# MAGI_sDIPBoard-Python.net
KiCad netlist of a schematic drawn in Altium Designer
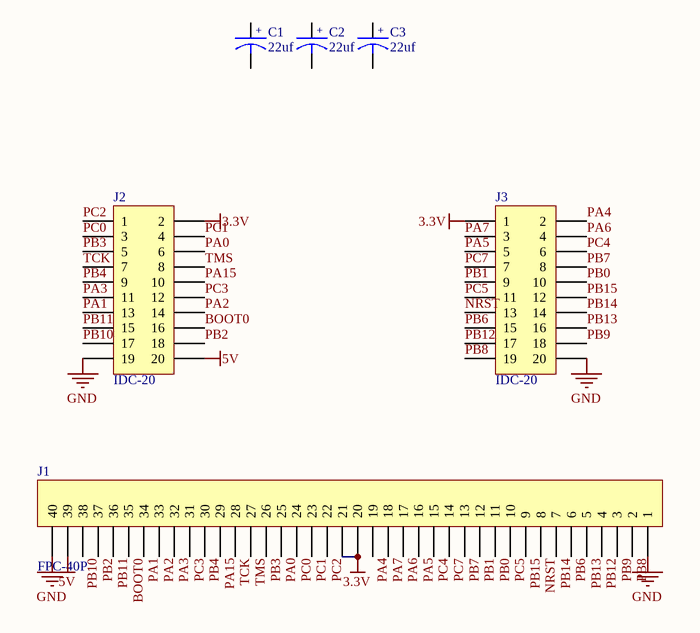
[diagram p0: MAGI'sDIPBoard-Python.SchDoc]

(export (version "E")
  (design (tool "Eeschema 10.0.6"))
  (components
    (comp (ref "C1")
      (value "22uf")
      (footprint "C1210_N")
      (description "Capacitor")
      (libsource (lib "电容器") (part "CAPACITOR POL"))
    )
    (comp (ref "C2")
      (value "22uf")
      (footprint "C1210_N")
      (description "Capacitor")
      (libsource (lib "电容器") (part "CAPACITOR POL"))
    )
    (comp (ref "C3")
      (value "22uf")
      (footprint "C1210_N")
      (description "Capacitor")
      (libsource (lib "电容器") (part "CAPACITOR POL"))
    )
    (comp (ref "J1")
      (value "FPC-40P")
      (footprint "FFC/SM0.5-2H40")
      (description "Connector")
      (libsource (lib "CON系列") (part "CON40"))
    )
    (comp (ref "J2") (value "IDC-20") (footprint "IDC-20") (libsource (lib "CON系列") (part "IDC-20")))
    (comp (ref "J3") (value "IDC-20") (footprint "IDC-20") (libsource (lib "CON系列") (part "IDC-20")))
  )
  (nets
    (net (code "1") (name "/BOOT0") (class "Default")
      (node (ref "J1") (pin "35") (pinfunction "35_35") (pintype "passive"))
      (node (ref "J2") (pin "16") (pinfunction "16_16") (pintype "passive"))
    )
    (net (code "2") (name "/NRST") (class "Default")
      (node (ref "J1") (pin "8") (pinfunction "8_8") (pintype "passive"))
      (node (ref "J3") (pin "13") (pinfunction "13_13") (pintype "passive"))
    )
    (net (code "3") (name "/PA0") (class "Default")
      (node (ref "J1") (pin "25") (pinfunction "25_25") (pintype "passive"))
      (node (ref "J2") (pin "6") (pinfunction "6_6") (pintype "passive"))
    )
    (net (code "4") (name "/PA1") (class "Default")
      (node (ref "J1") (pin "34") (pinfunction "34_34") (pintype "passive"))
      (node (ref "J2") (pin "13") (pinfunction "13_13") (pintype "passive"))
    )
    (net (code "5") (name "/PA2") (class "Default")
      (node (ref "J1") (pin "33") (pinfunction "33_33") (pintype "passive"))
      (node (ref "J2") (pin "14") (pinfunction "14_14") (pintype "passive"))
    )
    (net (code "6") (name "/PA3") (class "Default")
      (node (ref "J1") (pin "32") (pinfunction "32_32") (pintype "passive"))
      (node (ref "J2") (pin "11") (pinfunction "11_11") (pintype "passive"))
    )
    (net (code "7") (name "/PA4") (class "Default")
      (node (ref "J1") (pin "19") (pinfunction "19_19") (pintype "passive"))
      (node (ref "J3") (pin "2") (pinfunction "2_2") (pintype "passive"))
    )
    (net (code "8") (name "/PA5") (class "Default")
      (node (ref "J1") (pin "16") (pinfunction "16_16") (pintype "passive"))
      (node (ref "J3") (pin "5") (pinfunction "5_5") (pintype "passive"))
    )
    (net (code "9") (name "/PA6") (class "Default")
      (node (ref "J1") (pin "17") (pinfunction "17_17") (pintype "passive"))
      (node (ref "J3") (pin "4") (pinfunction "4_4") (pintype "passive"))
    )
    (net (code "10") (name "/PA7") (class "Default")
      (node (ref "J1") (pin "18") (pinfunction "18_18") (pintype "passive"))
      (node (ref "J3") (pin "3") (pinfunction "3_3") (pintype "passive"))
    )
    (net (code "11") (name "/PA15") (class "Default")
      (node (ref "J1") (pin "29") (pinfunction "29_29") (pintype "passive"))
      (node (ref "J2") (pin "10") (pinfunction "10_10") (pintype "passive"))
    )
    (net (code "12") (name "/PB0") (class "Default")
      (node (ref "J1") (pin "11") (pinfunction "11_11") (pintype "passive"))
      (node (ref "J3") (pin "10") (pinfunction "10_10") (pintype "passive"))
    )
    (net (code "13") (name "/PB1") (class "Default")
      (node (ref "J1") (pin "12") (pinfunction "12_12") (pintype "passive"))
      (node (ref "J3") (pin "9") (pinfunction "9_9") (pintype "passive"))
    )
    (net (code "14") (name "/PB2") (class "Default")
      (node (ref "J1") (pin "37") (pinfunction "37_37") (pintype "passive"))
      (node (ref "J2") (pin "18") (pinfunction "18_18") (pintype "passive"))
    )
    (net (code "15") (name "/PB3") (class "Default")
      (node (ref "J1") (pin "26") (pinfunction "26_26") (pintype "passive"))
      (node (ref "J2") (pin "5") (pinfunction "5_5") (pintype "passive"))
    )
    (net (code "16") (name "/PB4") (class "Default")
      (node (ref "J1") (pin "30") (pinfunction "30_30") (pintype "passive"))
      (node (ref "J2") (pin "9") (pinfunction "9_9") (pintype "passive"))
    )
    (net (code "17") (name "/PB6") (class "Default")
      (node (ref "J1") (pin "6") (pinfunction "6_6") (pintype "passive"))
      (node (ref "J3") (pin "15") (pinfunction "15_15") (pintype "passive"))
    )
    (net (code "18") (name "/PB7") (class "Default")
      (node (ref "J1") (pin "13") (pinfunction "13_13") (pintype "passive"))
      (node (ref "J3") (pin "8") (pinfunction "8_8") (pintype "passive"))
    )
    (net (code "19") (name "/PB8") (class "Default")
      (node (ref "J1") (pin "2") (pinfunction "2_2") (pintype "passive"))
      (node (ref "J3") (pin "19") (pinfunction "19_19") (pintype "passive"))
    )
    (net (code "20") (name "/PB9") (class "Default")
      (node (ref "J1") (pin "3") (pinfunction "3_3") (pintype "passive"))
      (node (ref "J3") (pin "18") (pinfunction "18_18") (pintype "passive"))
    )
    (net (code "21") (name "/PB10") (class "Default")
      (node (ref "J1") (pin "38") (pinfunction "38_38") (pintype "passive"))
      (node (ref "J2") (pin "17") (pinfunction "17_17") (pintype "passive"))
    )
    (net (code "22") (name "/PB11") (class "Default")
      (node (ref "J1") (pin "36") (pinfunction "36_36") (pintype "passive"))
      (node (ref "J2") (pin "15") (pinfunction "15_15") (pintype "passive"))
    )
    (net (code "23") (name "/PB12") (class "Default")
      (node (ref "J1") (pin "4") (pinfunction "4_4") (pintype "passive"))
      (node (ref "J3") (pin "17") (pinfunction "17_17") (pintype "passive"))
    )
    (net (code "24") (name "/PB13") (class "Default")
      (node (ref "J1") (pin "5") (pinfunction "5_5") (pintype "passive"))
      (node (ref "J3") (pin "16") (pinfunction "16_16") (pintype "passive"))
    )
    (net (code "25") (name "/PB14") (class "Default")
      (node (ref "J1") (pin "7") (pinfunction "7_7") (pintype "passive"))
      (node (ref "J3") (pin "14") (pinfunction "14_14") (pintype "passive"))
    )
    (net (code "26") (name "/PB15") (class "Default")
      (node (ref "J1") (pin "9") (pinfunction "9_9") (pintype "passive"))
      (node (ref "J3") (pin "12") (pinfunction "12_12") (pintype "passive"))
    )
    (net (code "27") (name "/PC0") (class "Default")
      (node (ref "J1") (pin "24") (pinfunction "24_24") (pintype "passive"))
      (node (ref "J2") (pin "3") (pinfunction "3_3") (pintype "passive"))
    )
    (net (code "28") (name "/PC1") (class "Default")
      (node (ref "J1") (pin "23") (pinfunction "23_23") (pintype "passive"))
      (node (ref "J2") (pin "4") (pinfunction "4_4") (pintype "passive"))
    )
    (net (code "29") (name "/PC2") (class "Default")
      (node (ref "J1") (pin "22") (pinfunction "22_22") (pintype "passive"))
      (node (ref "J2") (pin "1") (pinfunction "1_1") (pintype "passive"))
    )
    (net (code "30") (name "/PC3") (class "Default")
      (node (ref "J1") (pin "31") (pinfunction "31_31") (pintype "passive"))
      (node (ref "J2") (pin "12") (pinfunction "12_12") (pintype "passive"))
    )
    (net (code "31") (name "/PC4") (class "Default")
      (node (ref "J1") (pin "15") (pinfunction "15_15") (pintype "passive"))
      (node (ref "J3") (pin "6") (pinfunction "6_6") (pintype "passive"))
    )
    (net (code "32") (name "/PC5") (class "Default")
      (node (ref "J1") (pin "10") (pinfunction "10_10") (pintype "passive"))
      (node (ref "J3") (pin "11") (pinfunction "11_11") (pintype "passive"))
    )
    (net (code "33") (name "/PC7") (class "Default")
      (node (ref "J1") (pin "14") (pinfunction "14_14") (pintype "passive"))
      (node (ref "J3") (pin "7") (pinfunction "7_7") (pintype "passive"))
    )
    (net (code "34") (name "/TCK") (class "Default")
      (node (ref "J1") (pin "28") (pinfunction "28_28") (pintype "passive"))
      (node (ref "J2") (pin "7") (pinfunction "7_7") (pintype "passive"))
    )
    (net (code "35") (name "/TMS") (class "Default")
      (node (ref "J1") (pin "27") (pinfunction "27_27") (pintype "passive"))
      (node (ref "J2") (pin "8") (pinfunction "8_8") (pintype "passive"))
    )
    (net (code "36") (name "3.3V") (class "Default")
      (node (ref "J1") (pin "20") (pinfunction "20_20") (pintype "passive"))
      (node (ref "J1") (pin "21") (pinfunction "21_21") (pintype "passive"))
      (node (ref "J2") (pin "2") (pinfunction "2_2") (pintype "passive"))
      (node (ref "J3") (pin "1") (pinfunction "1_1") (pintype "passive"))
    )
    (net (code "37") (name "5V") (class "Default")
      (node (ref "J1") (pin "39") (pinfunction "39_39") (pintype "passive"))
      (node (ref "J2") (pin "20") (pinfunction "20_20") (pintype "passive"))
    )
    (net (code "38") (name "GND") (class "Default")
      (node (ref "J1") (pin "1") (pinfunction "1_1") (pintype "passive"))
      (node (ref "J1") (pin "40") (pinfunction "40_40") (pintype "passive"))
      (node (ref "J2") (pin "19") (pinfunction "19_19") (pintype "passive"))
      (node (ref "J3") (pin "20") (pinfunction "20_20") (pintype "passive"))
    )
    (net (code "39") (name "unconnected-(C1-Pad1)") (class "Default")
      (node (ref "C1") (pin "1") (pinfunction "1_1") (pintype "passive"))
    )
    (net (code "40") (name "unconnected-(C1-Pad2)") (class "Default")
      (node (ref "C1") (pin "2") (pinfunction "2_2") (pintype "passive"))
    )
    (net (code "41") (name "unconnected-(C2-Pad1)") (class "Default")
      (node (ref "C2") (pin "1") (pinfunction "1_1") (pintype "passive"))
    )
    (net (code "42") (name "unconnected-(C2-Pad2)") (class "Default")
      (node (ref "C2") (pin "2") (pinfunction "2_2") (pintype "passive"))
    )
    (net (code "43") (name "unconnected-(C3-Pad1)") (class "Default")
      (node (ref "C3") (pin "1") (pinfunction "1_1") (pintype "passive"))
    )
    (net (code "44") (name "unconnected-(C3-Pad2)") (class "Default")
      (node (ref "C3") (pin "2") (pinfunction "2_2") (pintype "passive"))
    )
  )
)
